# Sabhya_USB_HUb.net
KiCad netlist of a schematic drawn in EasyEDA Pro
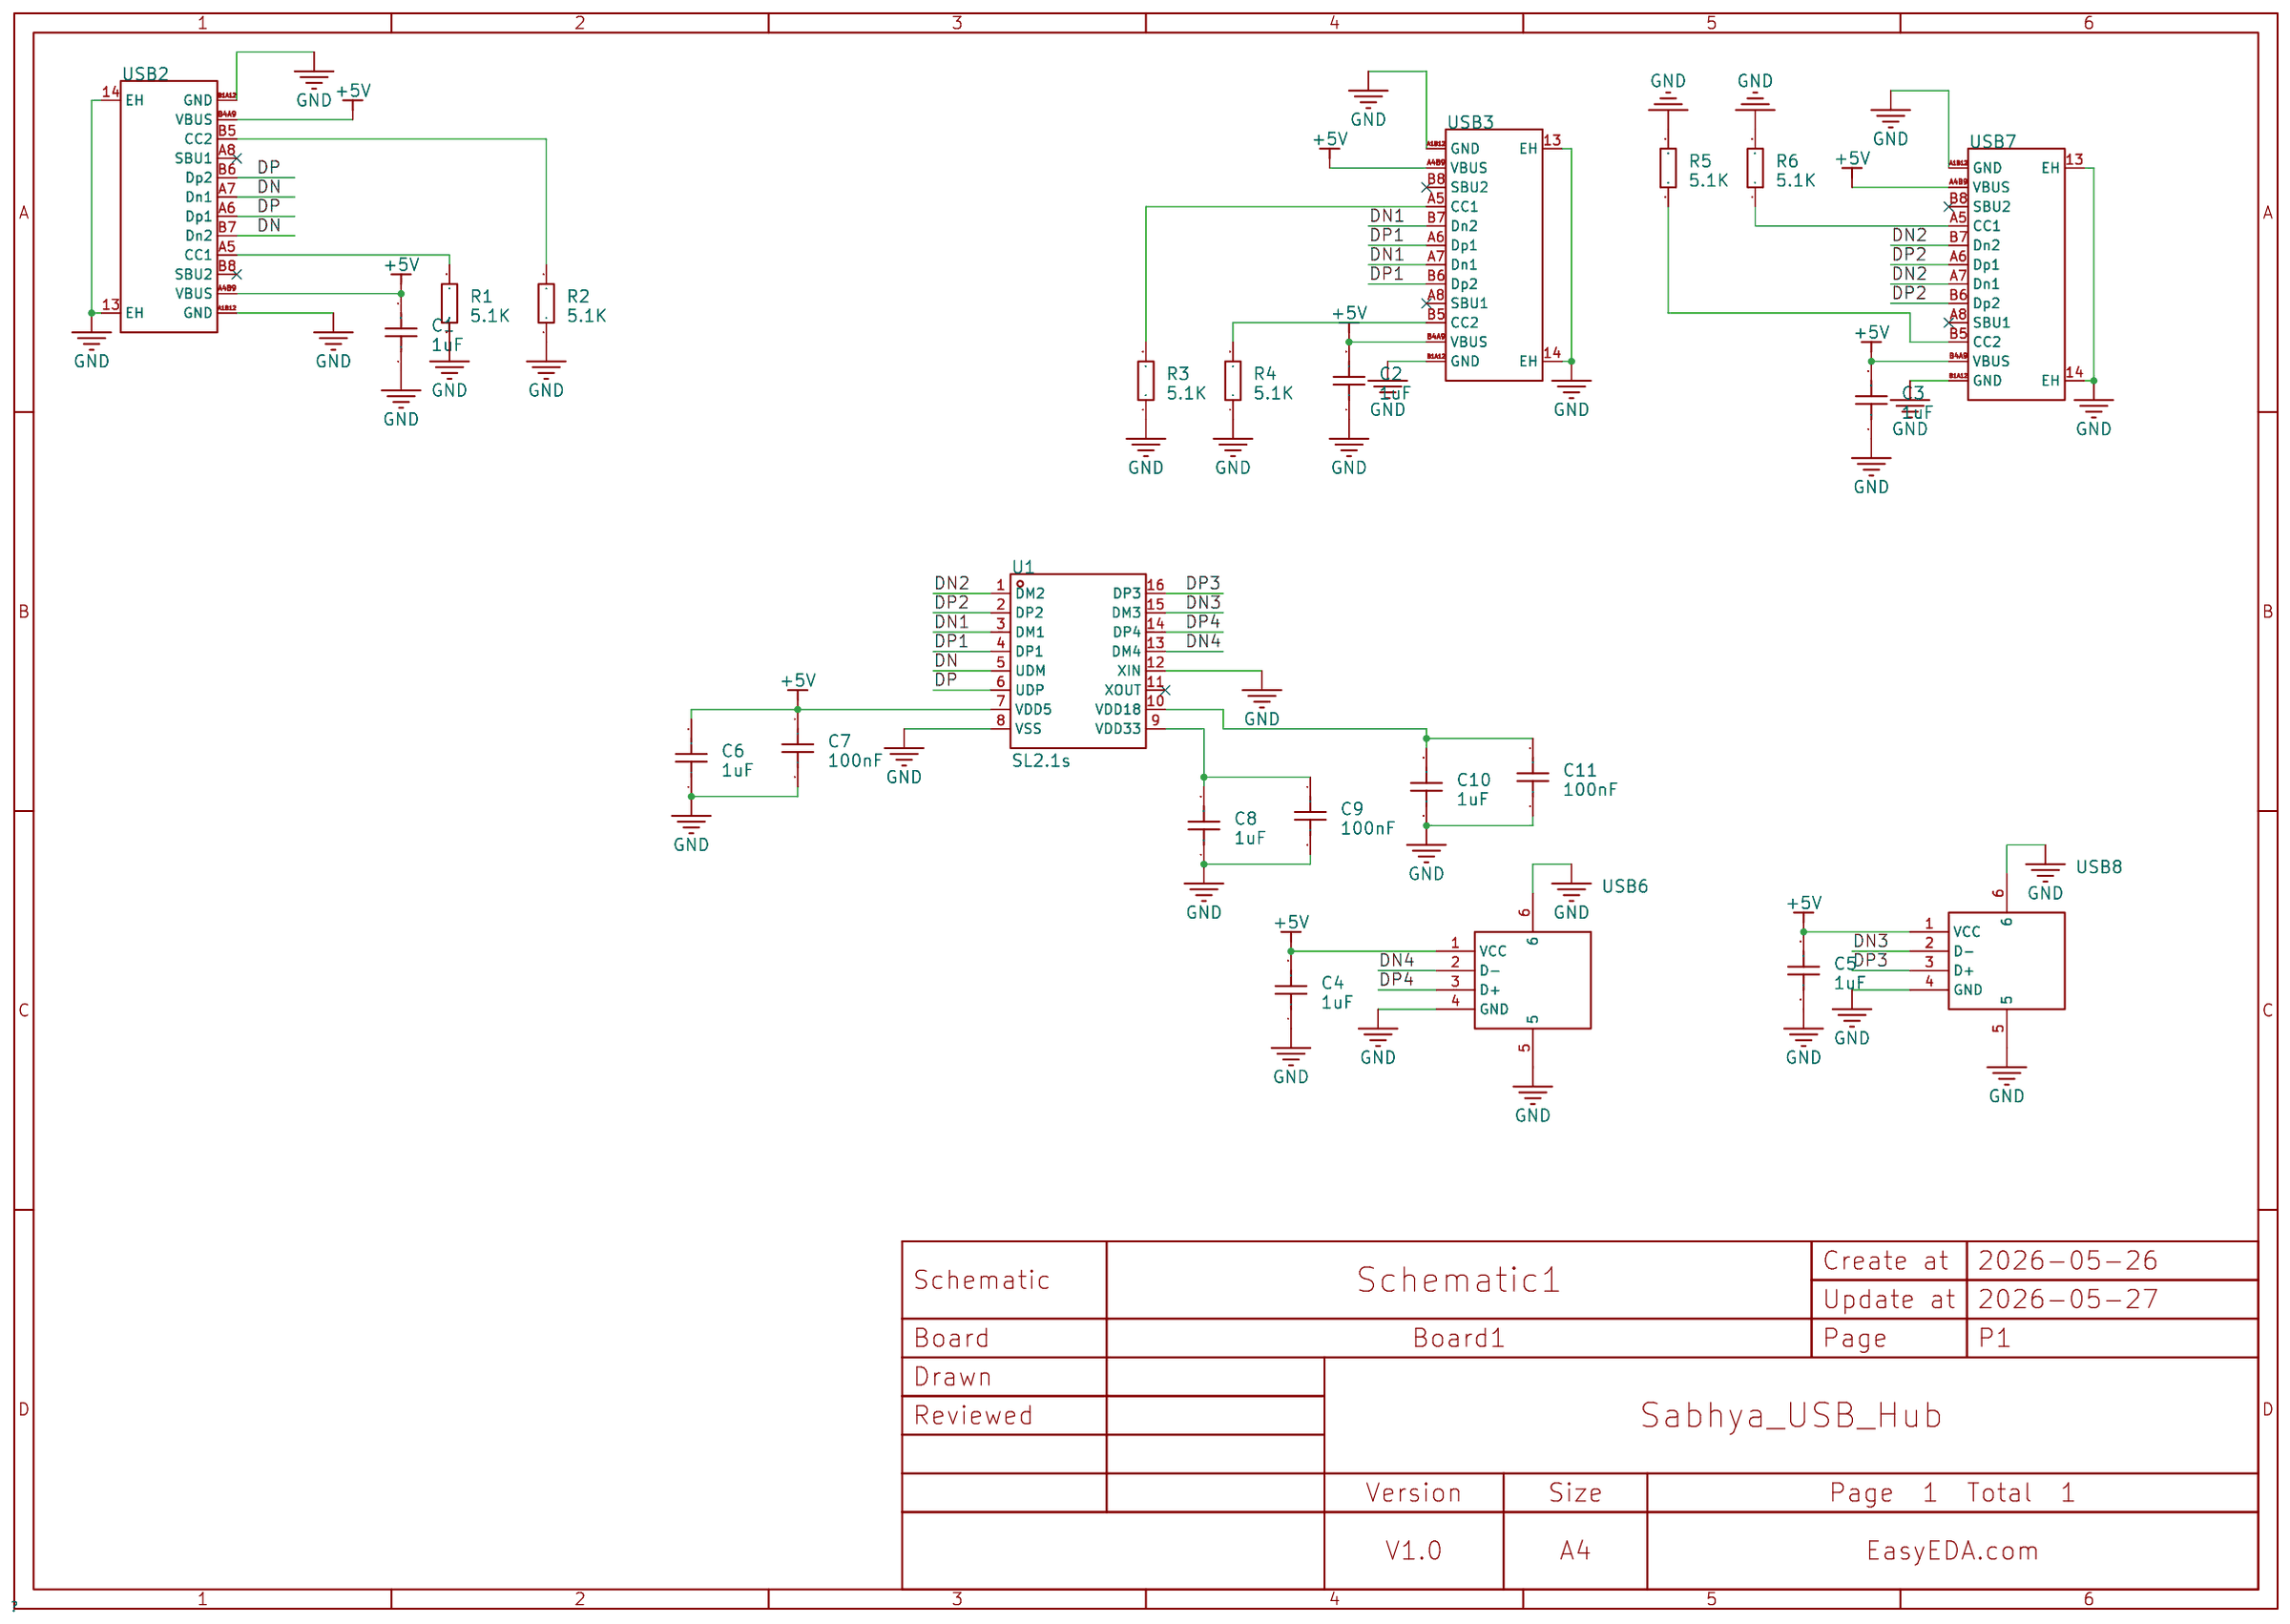
[diagram p0: schematic sheet]

(export (version "E")
  (design (tool "Eeschema 10.0.6"))
  (components
    (comp (ref "C1")
      (value "1uF")
      (footprint "easyedapro:C0603")
      (fields
        (field (name "Manufacturer Part") "CL10A105KB8NNNC")
        (field (name "Manufacturer") "SAMSUNG(三星)")
        (field (name "Tolerance") "±10%")
      )
      (libsource (lib "easyedapro") (part "CL10A105KB8NNNC"))
    )
    (comp (ref "C2")
      (value "1uF")
      (footprint "easyedapro:C0603")
      (fields
        (field (name "Manufacturer Part") "CL10A105KB8NNNC")
        (field (name "Manufacturer") "SAMSUNG(三星)")
        (field (name "Tolerance") "±10%")
      )
      (libsource (lib "easyedapro") (part "CL10A105KB8NNNC"))
    )
    (comp (ref "C3")
      (value "1uF")
      (footprint "easyedapro:C0603")
      (fields
        (field (name "Manufacturer Part") "CL10A105KB8NNNC")
        (field (name "Manufacturer") "SAMSUNG(三星)")
        (field (name "Tolerance") "±10%")
      )
      (libsource (lib "easyedapro") (part "CL10A105KB8NNNC"))
    )
    (comp (ref "C4")
      (value "1uF")
      (footprint "easyedapro:C0603")
      (fields
        (field (name "Manufacturer Part") "CL10A105KB8NNNC")
        (field (name "Manufacturer") "SAMSUNG(三星)")
        (field (name "Tolerance") "±10%")
      )
      (libsource (lib "easyedapro") (part "CL10A105KB8NNNC"))
    )
    (comp (ref "C5")
      (value "1uF")
      (footprint "easyedapro:C0603")
      (fields
        (field (name "Manufacturer Part") "CL10A105KB8NNNC")
        (field (name "Manufacturer") "SAMSUNG(三星)")
        (field (name "Tolerance") "±10%")
      )
      (libsource (lib "easyedapro") (part "CL10A105KB8NNNC"))
    )
    (comp (ref "C6")
      (value "1uF")
      (footprint "easyedapro:C0603")
      (fields
        (field (name "Manufacturer Part") "CL10A105KB8NNNC")
        (field (name "Manufacturer") "SAMSUNG(三星)")
        (field (name "Tolerance") "±10%")
      )
      (libsource (lib "easyedapro") (part "CL10A105KB8NNNC"))
    )
    (comp (ref "C7")
      (value "100nF")
      (footprint "easyedapro:CAP-TH_L7.4-W2.3-P5.08-D0.6")
      (fields (field (name "Manufacturer Part") "CAPR500-350X720X850100nF100V"))
      (libsource (lib "easyedapro") (part "CAPR500-350X720X850100NF100V"))
    )
    (comp (ref "C8")
      (value "1uF")
      (footprint "easyedapro:C0603")
      (fields
        (field (name "Manufacturer Part") "CL10A105KB8NNNC")
        (field (name "Manufacturer") "SAMSUNG(三星)")
        (field (name "Tolerance") "±10%")
      )
      (libsource (lib "easyedapro") (part "CL10A105KB8NNNC"))
    )
    (comp (ref "C9")
      (value "100nF")
      (footprint "easyedapro:CAP-TH_L7.4-W2.3-P5.08-D0.6")
      (fields (field (name "Manufacturer Part") "CAPR500-350X720X850100nF100V"))
      (libsource (lib "easyedapro") (part "CAPR500-350X720X850100NF100V"))
    )
    (comp (ref "C10")
      (value "1uF")
      (footprint "easyedapro:C0603")
      (fields
        (field (name "Manufacturer Part") "CL10A105KB8NNNC")
        (field (name "Manufacturer") "SAMSUNG(三星)")
        (field (name "Tolerance") "±10%")
      )
      (libsource (lib "easyedapro") (part "CL10A105KB8NNNC"))
    )
    (comp (ref "C11")
      (value "100nF")
      (footprint "easyedapro:CAP-TH_L7.4-W2.3-P5.08-D0.6")
      (fields (field (name "Manufacturer Part") "CAPR500-350X720X850100nF100V"))
      (libsource (lib "easyedapro") (part "CAPR500-350X720X850100NF100V"))
    )
    (comp (ref "R1")
      (value "5.1K")
      (footprint "easyedapro:R0603")
      (libsource (lib "easyedapro") (part "Res"))
    )
    (comp (ref "R2")
      (value "5.1K")
      (footprint "easyedapro:R0603")
      (libsource (lib "easyedapro") (part "Res"))
    )
    (comp (ref "R3")
      (value "5.1K")
      (footprint "easyedapro:R0603")
      (libsource (lib "easyedapro") (part "Res"))
    )
    (comp (ref "R4")
      (value "5.1K")
      (footprint "easyedapro:R0603")
      (libsource (lib "easyedapro") (part "Res"))
    )
    (comp (ref "R5")
      (value "5.1K")
      (footprint "easyedapro:R0603")
      (libsource (lib "easyedapro") (part "Res"))
    )
    (comp (ref "R6")
      (value "5.1K")
      (footprint "easyedapro:R0603")
      (libsource (lib "easyedapro") (part "Res"))
    )
    (comp (ref "U1")
      (value "SL2.1s")
      (footprint "easyedapro:SSOP-16_L4.6-W2.6-P0.53-LS4.0-BL")
      (fields (field (name "Manufacturer") "CoreChips(和芯润德)"))
      (libsource (lib "easyedapro") (part "SL2.1S"))
    )
    (comp (ref "USB2")
      (value "TYPE-C 16PIN 2MD(073)")
      (footprint "easyedapro:USB-C-SMD_TYPE-C-16PIN-2MD-073")
      (fields (field (name "Manufacturer") "SHOU HAN(首韩)"))
      (libsource (lib "easyedapro") (part "TYPE-C 16PIN 2MD(073)"))
    )
    (comp (ref "USB3")
      (value "TYPE-C 16PIN 2MD(073)")
      (footprint "easyedapro:USB-C-SMD_TYPE-C-16PIN-2MD-073")
      (fields (field (name "Manufacturer") "SHOU HAN(首韩)"))
      (libsource (lib "easyedapro") (part "TYPE-C 16PIN 2MD(073)"))
    )
    (comp (ref "USB6")
      (value "10.0 QHHTZB6.3")
      (footprint "easyedapro:USB-A-TH_10.0QHHTZB6.3")
      (fields (field (name "Manufacturer") "SHOU HAN(首韩)"))
      (libsource (lib "easyedapro") (part "10.0 QHHTZB6.3"))
    )
    (comp (ref "USB7")
      (value "TYPE-C 16PIN 2MD(073)")
      (footprint "easyedapro:USB-C-SMD_TYPE-C-16PIN-2MD-073")
      (fields (field (name "Manufacturer") "SHOU HAN(首韩)"))
      (libsource (lib "easyedapro") (part "TYPE-C 16PIN 2MD(073)"))
    )
    (comp (ref "USB8")
      (value "10.0 QHHTZB6.3")
      (footprint "easyedapro:USB-A-TH_10.0QHHTZB6.3")
      (fields (field (name "Manufacturer") "SHOU HAN(首韩)"))
      (libsource (lib "easyedapro") (part "10.0 QHHTZB6.3"))
    )
  )
  (nets
    (net (code "1") (name "+5V") (class "Default")
      (node (ref "C1") (pin "2") (pinfunction "2_2") (pintype "unspecified"))
      (node (ref "C2") (pin "2") (pinfunction "2_2") (pintype "unspecified"))
      (node (ref "C3") (pin "2") (pinfunction "2_2") (pintype "unspecified"))
      (node (ref "C4") (pin "2") (pinfunction "2_2") (pintype "unspecified"))
      (node (ref "C5") (pin "2") (pinfunction "2_2") (pintype "unspecified"))
      (node (ref "C6") (pin "2") (pinfunction "2_2") (pintype "unspecified"))
      (node (ref "C7") (pin "1") (pinfunction "1_1") (pintype "unspecified"))
      (node (ref "U1") (pin "7") (pinfunction "VDD5_7") (pintype "unspecified"))
      (node (ref "USB2") (pin "A4B9") (pinfunction "VBUS_A4B9") (pintype "unspecified"))
      (node (ref "USB2") (pin "B4A9") (pinfunction "VBUS_B4A9") (pintype "unspecified"))
      (node (ref "USB3") (pin "A4B9") (pinfunction "VBUS_A4B9") (pintype "unspecified"))
      (node (ref "USB3") (pin "B4A9") (pinfunction "VBUS_B4A9") (pintype "unspecified"))
      (node (ref "USB6") (pin "1") (pinfunction "VCC_1") (pintype "unspecified"))
      (node (ref "USB7") (pin "A4B9") (pinfunction "VBUS_A4B9") (pintype "unspecified"))
      (node (ref "USB7") (pin "B4A9") (pinfunction "VBUS_B4A9") (pintype "unspecified"))
      (node (ref "USB8") (pin "1") (pinfunction "VCC_1") (pintype "unspecified"))
    )
    (net (code "2") (name "/DN") (class "Default")
      (node (ref "U1") (pin "5") (pinfunction "UDM_5") (pintype "unspecified"))
      (node (ref "USB2") (pin "A7") (pinfunction "Dn1_A7") (pintype "unspecified"))
      (node (ref "USB2") (pin "B7") (pinfunction "Dn2_B7") (pintype "unspecified"))
    )
    (net (code "3") (name "/DN1") (class "Default")
      (node (ref "U1") (pin "3") (pinfunction "DM1_3") (pintype "unspecified"))
      (node (ref "USB3") (pin "A7") (pinfunction "Dn1_A7") (pintype "unspecified"))
      (node (ref "USB3") (pin "B7") (pinfunction "Dn2_B7") (pintype "unspecified"))
    )
    (net (code "4") (name "/DN2") (class "Default")
      (node (ref "U1") (pin "1") (pinfunction "DM2_1") (pintype "unspecified"))
      (node (ref "USB7") (pin "A7") (pinfunction "Dn1_A7") (pintype "unspecified"))
      (node (ref "USB7") (pin "B7") (pinfunction "Dn2_B7") (pintype "unspecified"))
    )
    (net (code "5") (name "/DN3") (class "Default")
      (node (ref "U1") (pin "15") (pinfunction "DM3_15") (pintype "unspecified"))
      (node (ref "USB8") (pin "2") (pinfunction "D-_2") (pintype "unspecified"))
    )
    (net (code "6") (name "/DN4") (class "Default")
      (node (ref "U1") (pin "13") (pinfunction "DM4_13") (pintype "unspecified"))
      (node (ref "USB6") (pin "2") (pinfunction "D-_2") (pintype "unspecified"))
    )
    (net (code "7") (name "/DP") (class "Default")
      (node (ref "U1") (pin "6") (pinfunction "UDP_6") (pintype "unspecified"))
      (node (ref "USB2") (pin "A6") (pinfunction "Dp1_A6") (pintype "unspecified"))
      (node (ref "USB2") (pin "B6") (pinfunction "Dp2_B6") (pintype "unspecified"))
    )
    (net (code "8") (name "/DP1") (class "Default")
      (node (ref "U1") (pin "4") (pinfunction "DP1_4") (pintype "unspecified"))
      (node (ref "USB3") (pin "A6") (pinfunction "Dp1_A6") (pintype "unspecified"))
      (node (ref "USB3") (pin "B6") (pinfunction "Dp2_B6") (pintype "unspecified"))
    )
    (net (code "9") (name "/DP2") (class "Default")
      (node (ref "U1") (pin "2") (pinfunction "DP2_2") (pintype "unspecified"))
      (node (ref "USB7") (pin "A6") (pinfunction "Dp1_A6") (pintype "unspecified"))
      (node (ref "USB7") (pin "B6") (pinfunction "Dp2_B6") (pintype "unspecified"))
    )
    (net (code "10") (name "/DP3") (class "Default")
      (node (ref "U1") (pin "16") (pinfunction "DP3_16") (pintype "unspecified"))
      (node (ref "USB8") (pin "3") (pinfunction "D+_3") (pintype "unspecified"))
    )
    (net (code "11") (name "/DP4") (class "Default")
      (node (ref "U1") (pin "14") (pinfunction "DP4_14") (pintype "unspecified"))
      (node (ref "USB6") (pin "3") (pinfunction "D+_3") (pintype "unspecified"))
    )
    (net (code "12") (name "GND") (class "Default")
      (node (ref "C1") (pin "1") (pinfunction "1_1") (pintype "unspecified"))
      (node (ref "C10") (pin "1") (pinfunction "1_1") (pintype "unspecified"))
      (node (ref "C11") (pin "2") (pinfunction "2_2") (pintype "unspecified"))
      (node (ref "C2") (pin "1") (pinfunction "1_1") (pintype "unspecified"))
      (node (ref "C3") (pin "1") (pinfunction "1_1") (pintype "unspecified"))
      (node (ref "C4") (pin "1") (pinfunction "1_1") (pintype "unspecified"))
      (node (ref "C5") (pin "1") (pinfunction "1_1") (pintype "unspecified"))
      (node (ref "C6") (pin "1") (pinfunction "1_1") (pintype "unspecified"))
      (node (ref "C7") (pin "2") (pinfunction "2_2") (pintype "unspecified"))
      (node (ref "C8") (pin "1") (pinfunction "1_1") (pintype "unspecified"))
      (node (ref "C9") (pin "2") (pinfunction "2_2") (pintype "unspecified"))
      (node (ref "R1") (pin "1") (pinfunction "1_1") (pintype "input"))
      (node (ref "R2") (pin "1") (pinfunction "1_1") (pintype "input"))
      (node (ref "R3") (pin "1") (pinfunction "1_1") (pintype "input"))
      (node (ref "R4") (pin "1") (pinfunction "1_1") (pintype "input"))
      (node (ref "R5") (pin "2") (pinfunction "2_2") (pintype "input"))
      (node (ref "R6") (pin "2") (pinfunction "2_2") (pintype "input"))
      (node (ref "U1") (pin "12") (pinfunction "XIN_12") (pintype "unspecified"))
      (node (ref "U1") (pin "8") (pinfunction "VSS_8") (pintype "unspecified"))
      (node (ref "USB2") (pin "13") (pinfunction "EH_13") (pintype "unspecified"))
      (node (ref "USB2") (pin "14") (pinfunction "EH_14") (pintype "unspecified"))
      (node (ref "USB2") (pin "A1B12") (pinfunction "GND_A1B12") (pintype "unspecified"))
      (node (ref "USB2") (pin "B1A12") (pinfunction "GND_B1A12") (pintype "unspecified"))
      (node (ref "USB3") (pin "13") (pinfunction "EH_13") (pintype "unspecified"))
      (node (ref "USB3") (pin "14") (pinfunction "EH_14") (pintype "unspecified"))
      (node (ref "USB3") (pin "A1B12") (pinfunction "GND_A1B12") (pintype "unspecified"))
      (node (ref "USB3") (pin "B1A12") (pinfunction "GND_B1A12") (pintype "unspecified"))
      (node (ref "USB6") (pin "4") (pinfunction "GND_4") (pintype "unspecified"))
      (node (ref "USB6") (pin "5") (pinfunction "5_5") (pintype "unspecified"))
      (node (ref "USB6") (pin "6") (pinfunction "6_6") (pintype "unspecified"))
      (node (ref "USB7") (pin "13") (pinfunction "EH_13") (pintype "unspecified"))
      (node (ref "USB7") (pin "14") (pinfunction "EH_14") (pintype "unspecified"))
      (node (ref "USB7") (pin "A1B12") (pinfunction "GND_A1B12") (pintype "unspecified"))
      (node (ref "USB7") (pin "B1A12") (pinfunction "GND_B1A12") (pintype "unspecified"))
      (node (ref "USB8") (pin "4") (pinfunction "GND_4") (pintype "unspecified"))
      (node (ref "USB8") (pin "5") (pinfunction "5_5") (pintype "unspecified"))
      (node (ref "USB8") (pin "6") (pinfunction "6_6") (pintype "unspecified"))
    )
    (net (code "13") (name "Net-(U1-VDD18)") (class "Default")
      (node (ref "C10") (pin "2") (pinfunction "2_2") (pintype "unspecified"))
      (node (ref "C11") (pin "1") (pinfunction "1_1") (pintype "unspecified"))
      (node (ref "U1") (pin "10") (pinfunction "VDD18_10") (pintype "unspecified"))
    )
    (net (code "14") (name "Net-(U1-VDD33)") (class "Default")
      (node (ref "C8") (pin "2") (pinfunction "2_2") (pintype "unspecified"))
      (node (ref "C9") (pin "1") (pinfunction "1_1") (pintype "unspecified"))
      (node (ref "U1") (pin "9") (pinfunction "VDD33_9") (pintype "unspecified"))
    )
    (net (code "15") (name "Net-(USB2-CC1)") (class "Default")
      (node (ref "R1") (pin "2") (pinfunction "2_2") (pintype "input"))
      (node (ref "USB2") (pin "A5") (pinfunction "CC1_A5") (pintype "unspecified"))
    )
    (net (code "16") (name "Net-(USB2-CC2)") (class "Default")
      (node (ref "R2") (pin "2") (pinfunction "2_2") (pintype "input"))
      (node (ref "USB2") (pin "B5") (pinfunction "CC2_B5") (pintype "unspecified"))
    )
    (net (code "17") (name "Net-(USB3-CC1)") (class "Default")
      (node (ref "R3") (pin "2") (pinfunction "2_2") (pintype "input"))
      (node (ref "USB3") (pin "A5") (pinfunction "CC1_A5") (pintype "unspecified"))
    )
    (net (code "18") (name "Net-(USB3-CC2)") (class "Default")
      (node (ref "R4") (pin "2") (pinfunction "2_2") (pintype "input"))
      (node (ref "USB3") (pin "B5") (pinfunction "CC2_B5") (pintype "unspecified"))
    )
    (net (code "19") (name "Net-(USB7-CC1)") (class "Default")
      (node (ref "R6") (pin "1") (pinfunction "1_1") (pintype "input"))
      (node (ref "USB7") (pin "A5") (pinfunction "CC1_A5") (pintype "unspecified"))
    )
    (net (code "20") (name "Net-(USB7-CC2)") (class "Default")
      (node (ref "R5") (pin "1") (pinfunction "1_1") (pintype "input"))
      (node (ref "USB7") (pin "B5") (pinfunction "CC2_B5") (pintype "unspecified"))
    )
    (net (code "21") (name "unconnected-(U1-XOUT-Pad11)") (class "Default")
      (node (ref "U1") (pin "11") (pinfunction "XOUT_11") (pintype "unspecified+no_connect"))
    )
    (net (code "22") (name "unconnected-(USB2-SBU1-PadA8)") (class "Default")
      (node (ref "USB2") (pin "A8") (pinfunction "SBU1_A8") (pintype "unspecified+no_connect"))
    )
    (net (code "23") (name "unconnected-(USB2-SBU2-PadB8)") (class "Default")
      (node (ref "USB2") (pin "B8") (pinfunction "SBU2_B8") (pintype "unspecified+no_connect"))
    )
    (net (code "24") (name "unconnected-(USB3-SBU1-PadA8)") (class "Default")
      (node (ref "USB3") (pin "A8") (pinfunction "SBU1_A8") (pintype "unspecified+no_connect"))
    )
    (net (code "25") (name "unconnected-(USB3-SBU2-PadB8)") (class "Default")
      (node (ref "USB3") (pin "B8") (pinfunction "SBU2_B8") (pintype "unspecified+no_connect"))
    )
    (net (code "26") (name "unconnected-(USB7-SBU1-PadA8)") (class "Default")
      (node (ref "USB7") (pin "A8") (pinfunction "SBU1_A8") (pintype "unspecified+no_connect"))
    )
    (net (code "27") (name "unconnected-(USB7-SBU2-PadB8)") (class "Default")
      (node (ref "USB7") (pin "B8") (pinfunction "SBU2_B8") (pintype "unspecified+no_connect"))
    )
  )
)
